# usb_adapter.net
KiCad netlist of a schematic drawn in EAGLE
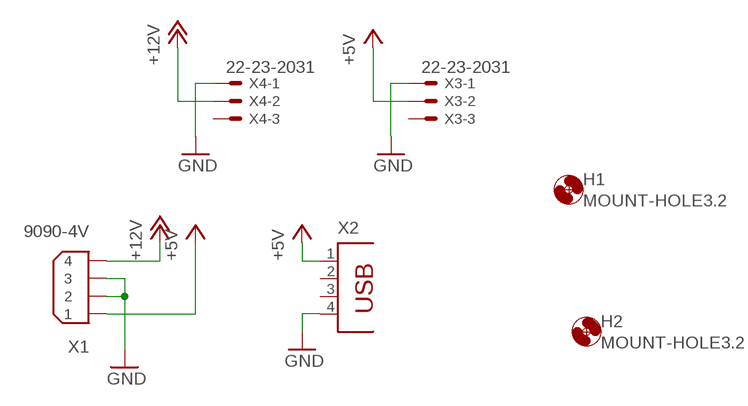
[diagram p0: schematic, sheet 1]

(export (version "E")
  (design (tool "Eeschema 10.0.6"))
  (components
    (comp (ref "H1")
      (value "MOUNT-HOLE3.2")
      (footprint "eagle-import:3,2")
      (libsource (lib "eagle-import") (part "MOUNT-HOLE3.2"))
    )
    (comp (ref "H2")
      (value "MOUNT-HOLE3.2")
      (footprint "eagle-import:3,2")
      (libsource (lib "eagle-import") (part "MOUNT-HOLE3.2"))
    )
    (comp (ref "X1")
      (value "9090-4V")
      (footprint "eagle-import:9090-4V")
      (libsource (lib "eagle-import") (part "9090-4V"))
    )
    (comp (ref "X2")
      (value "PN87520")
      (footprint "eagle-import:PN87520")
      (libsource (lib "eagle-import") (part "PN87520"))
    )
    (comp (ref "X3")
      (value "22-23-2031")
      (footprint "eagle-import:22-23-2031")
      (fields (field (name "MF") "MOLEX"))
      (libsource (lib "eagle-import") (part "22-23-2031"))
    )
    (comp (ref "X4")
      (value "22-23-2031")
      (footprint "eagle-import:22-23-2031")
      (fields (field (name "MF") "MOLEX"))
      (libsource (lib "eagle-import") (part "22-23-2031"))
    )
  )
  (nets
    (net (code "1") (name "+5V") (class "Default")
      (node (ref "X1") (pin "1") (pinfunction "1_1") (pintype "passive"))
      (node (ref "X2") (pin "1") (pinfunction "1_1") (pintype "passive"))
      (node (ref "X3") (pin "2") (pinfunction "S_2") (pintype "passive"))
    )
    (net (code "2") (name "+12V") (class "Default")
      (node (ref "X1") (pin "4") (pinfunction "4_4") (pintype "passive"))
      (node (ref "X4") (pin "2") (pinfunction "S_2") (pintype "passive"))
    )
    (net (code "3") (name "GND") (class "Default")
      (node (ref "X1") (pin "2") (pinfunction "2_2") (pintype "passive"))
      (node (ref "X1") (pin "3") (pinfunction "3_3") (pintype "passive"))
      (node (ref "X2") (pin "4") (pinfunction "4_4") (pintype "passive"))
      (node (ref "X3") (pin "1") (pinfunction "S_1") (pintype "passive"))
      (node (ref "X4") (pin "1") (pinfunction "S_1") (pintype "passive"))
    )
    (net (code "4") (name "unconnected-(X2-Pad2)") (class "Default")
      (node (ref "X2") (pin "2") (pinfunction "2_2") (pintype "passive"))
    )
    (net (code "5") (name "unconnected-(X2-Pad3)") (class "Default")
      (node (ref "X2") (pin "3") (pinfunction "3_3") (pintype "passive"))
    )
    (net (code "6") (name "unconnected-(X3C-S-Pad3)") (class "Default")
      (node (ref "X3") (pin "3") (pinfunction "S_3") (pintype "passive"))
    )
    (net (code "7") (name "unconnected-(X4C-S-Pad3)") (class "Default")
      (node (ref "X4") (pin "3") (pinfunction "S_3") (pintype "passive"))
    )
  )
)
